# PG04_SHEET2.net
KiCad netlist of a schematic drawn in Altium Designer
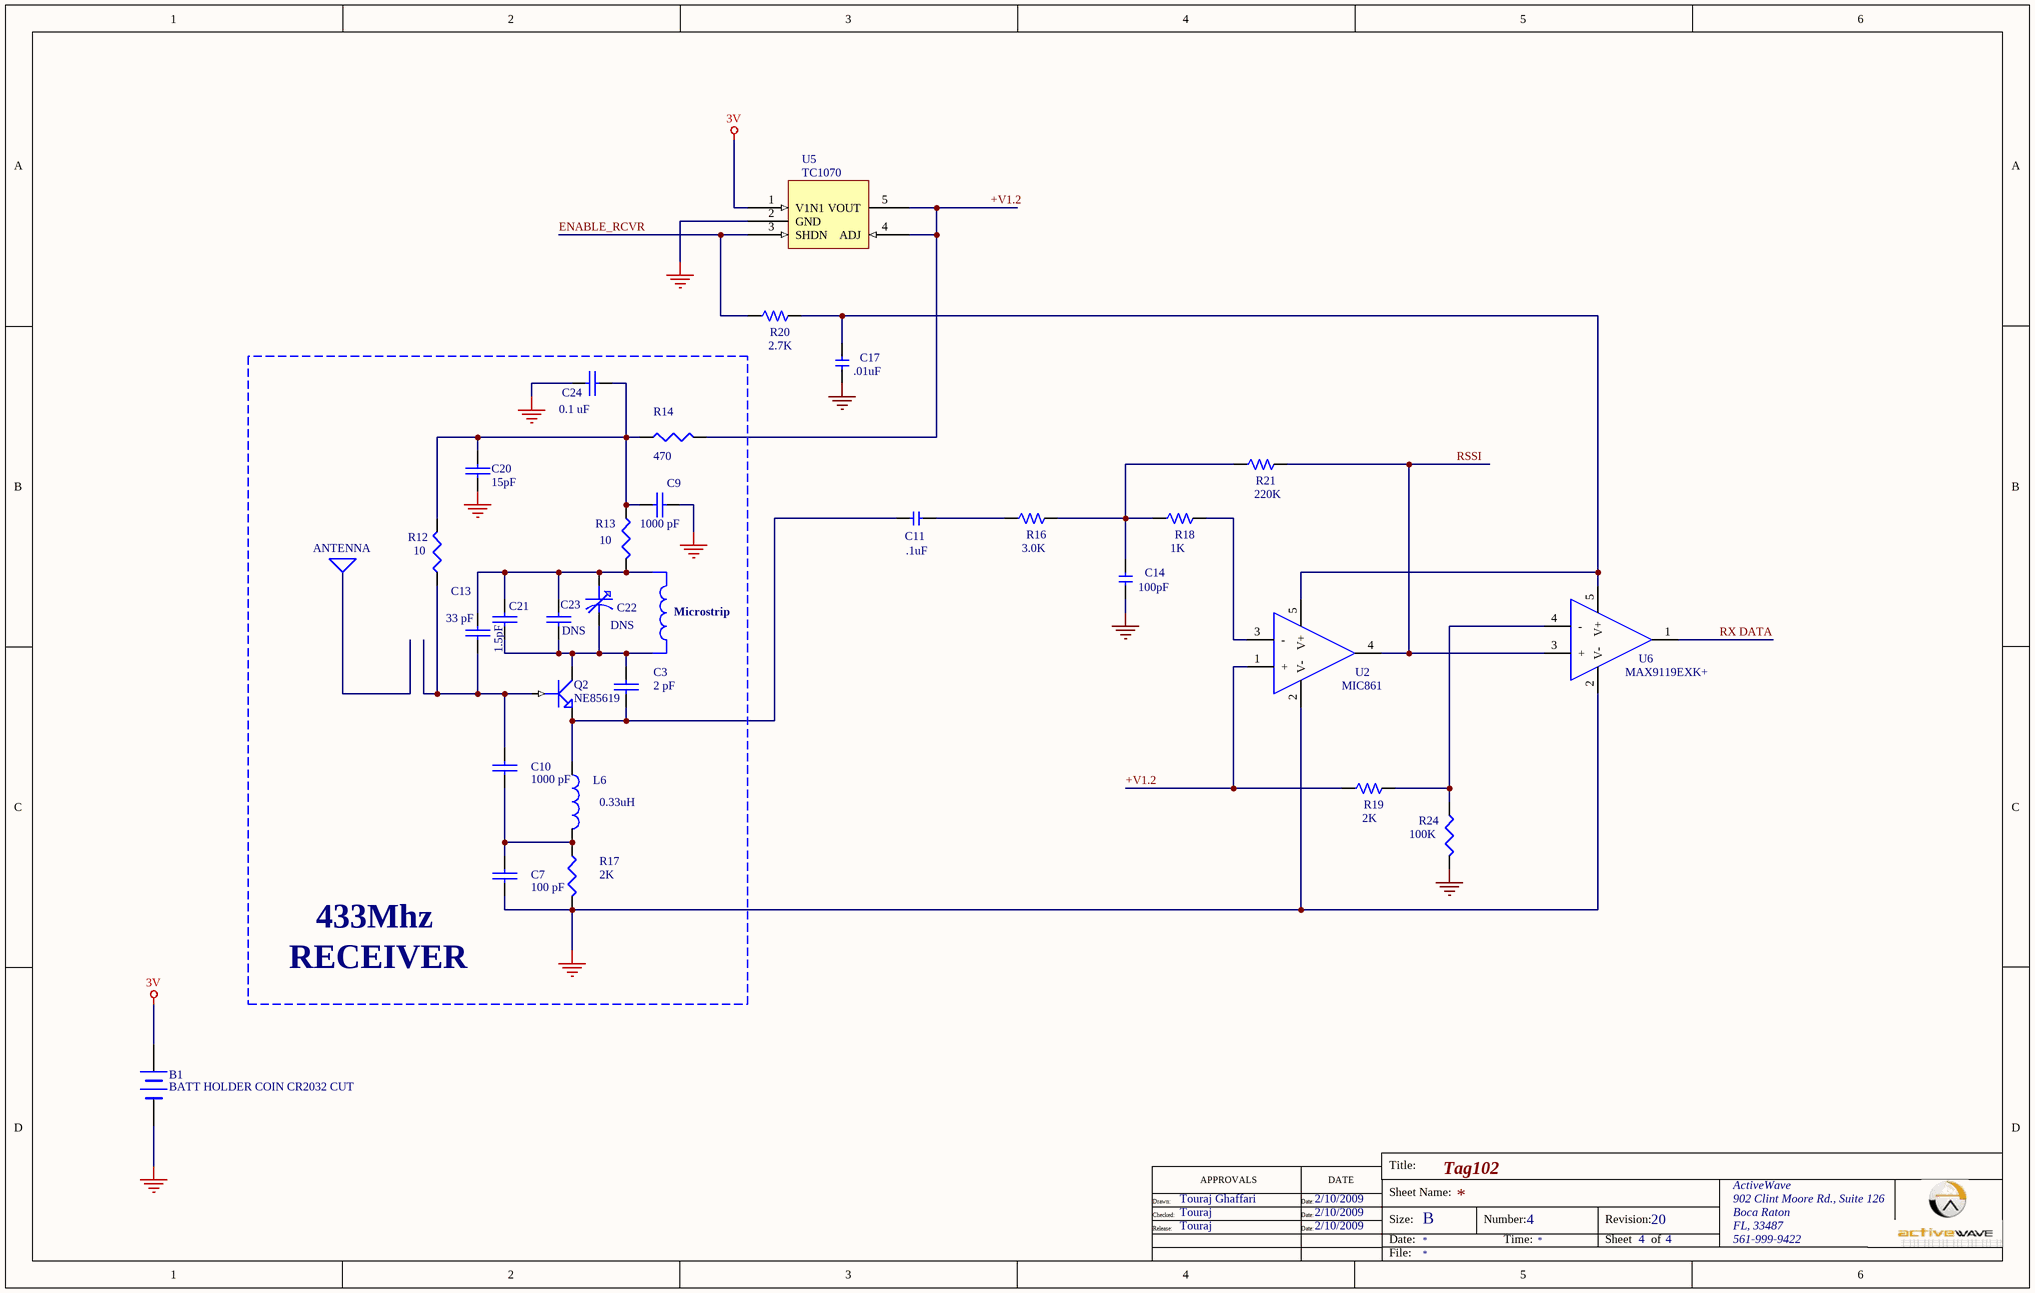
[diagram p0: PG04 SHEET2.schdoc]

(export (version "E")
  (design (tool "Eeschema 10.0.6"))
  (components
    (comp (ref "B1")
      (value "BATT HOLDER COIN CR2032 CUT")
      (footprint "BATT HOLDER COIN CR2032 CUT_020812")
      (description "Battery")
      (libsource (lib "*") (part "BATTERY"))
    )
    (comp (ref "C3")
      (value "2 pF")
      (footprint "0603")
      (description "Capacitor")
      (libsource (lib "*") (part "CAP"))
    )
    (comp (ref "C7")
      (value "100 pF")
      (footprint "0603")
      (description "Capacitor")
      (libsource (lib "*") (part "CAP"))
    )
    (comp (ref "C9")
      (value "1000 pF")
      (footprint "0603")
      (description "Capacitor")
      (libsource (lib "*") (part "CAP"))
    )
    (comp (ref "C10")
      (value "1000 pF")
      (footprint "0603")
      (description "Capacitor")
      (libsource (lib "*") (part "CAP"))
    )
    (comp (ref "C11") (value ".1uF") (footprint "0603") (libsource (lib "*") (part "C")))
    (comp (ref "C13")
      (value "33 pF")
      (footprint "0603")
      (description "Capacitor")
      (libsource (lib "*") (part "CAP"))
    )
    (comp (ref "C14") (value "100pF") (footprint "0603") (libsource (lib "*") (part "C")))
    (comp (ref "C17") (value ".01uF") (footprint "0603") (libsource (lib "*") (part "C")))
    (comp (ref "C20")
      (value "15pF")
      (footprint "0603")
      (description "Capacitor")
      (libsource (lib "*") (part "CAP"))
    )
    (comp (ref "C21")
      (value "1.5pF")
      (footprint "0603")
      (description "Capacitor")
      (libsource (lib "*") (part "CAP"))
    )
    (comp (ref "C22") (value "DNS") (footprint "0603") (libsource (lib "*") (part "CAPACITOR VAR")))
    (comp (ref "C23")
      (value "DNS")
      (footprint "0603")
      (description "Capacitor")
      (libsource (lib "*") (part "CAP"))
    )
    (comp (ref "C24")
      (value "0.1 uF")
      (footprint "0603")
      (description "Capacitor")
      (libsource (lib "*") (part "CAP"))
    )
    (comp (ref "L6") (value "0.33uH") (footprint "0603") (libsource (lib "*") (part "INDUCTOR")))
    (comp (ref "Q2")
      (value "NE85619")
      (footprint "3 PIN ULTRA SUPER MINI MOLD")
      (description "NPN Transistor")
      (libsource (lib "*") (part "NPN1"))
    )
    (comp (ref "R12") (value "10") (footprint "0603") (libsource (lib "*") (part "R")))
    (comp (ref "R13") (value "10") (footprint "0603") (libsource (lib "*") (part "R")))
    (comp (ref "R14") (value "470") (footprint "0603") (libsource (lib "*") (part "R")))
    (comp (ref "R16") (value "3.0K") (footprint "0603") (libsource (lib "") (part "R_1")))
    (comp (ref "R17") (value "2K") (footprint "0603") (libsource (lib "*") (part "RESISTOR")))
    (comp (ref "R18") (value "1K") (footprint "0603") (libsource (lib "") (part "R_1")))
    (comp (ref "R19") (value "2K") (footprint "0603") (libsource (lib "") (part "R_1")))
    (comp (ref "R20") (value "2.7K") (footprint "0603") (libsource (lib "") (part "R_1")))
    (comp (ref "R21") (value "220K") (footprint "0603") (libsource (lib "") (part "R_1")))
    (comp (ref "R24") (value "100K") (footprint "0603") (libsource (lib "*") (part "R")))
    (comp (ref "U2") (value "MIC861") (footprint "SC70") (libsource (lib "*") (part "OPAMP MIC861")))
    (comp (ref "U5") (value "TC1070") (footprint "SOT23-5A") (libsource (lib "*") (part "TC1070-2")))
    (comp (ref "U6")
      (value "MAX9119EXK+")
      (footprint "SC70")
      (libsource (lib "*") (part "COMPARATOR MAX9117"))
    )
  )
  (nets
    (net (code "1") (name "/+V1.2") (class "Default")
      (node (ref "R14") (pin "2") (pinfunction "2_2") (pintype "passive"))
      (node (ref "R19") (pin "1") (pinfunction "1_1") (pintype "passive"))
      (node (ref "U2") (pin "1") (pinfunction "+_1") (pintype "passive"))
      (node (ref "U5") (pin "4") (pinfunction "ADJ_4") (pintype "input"))
      (node (ref "U5") (pin "5") (pinfunction "VOUT_5") (pintype "power_in"))
    )
    (net (code "2") (name "/ENABLE_RCVR") (class "Default")
      (node (ref "R20") (pin "1") (pinfunction "1_1") (pintype "passive"))
      (node (ref "U5") (pin "3") (pinfunction "SHDN_3") (pintype "input"))
    )
    (net (code "3") (name "/RSSI") (class "Default")
      (node (ref "R21") (pin "2") (pinfunction "2_2") (pintype "passive"))
      (node (ref "U2") (pin "4") (pinfunction "OUT_4") (pintype "passive"))
      (node (ref "U6") (pin "3") (pinfunction "+_3") (pintype "passive"))
    )
    (net (code "4") (name "/RX DATA") (class "Default")
      (node (ref "U6") (pin "1") (pinfunction "OUT_1") (pintype "passive"))
    )
    (net (code "5") (name "3V") (class "Default")
      (node (ref "B1") (pin "2") (pinfunction "+_2") (pintype "passive"))
      (node (ref "U5") (pin "1") (pinfunction "V1N1_1") (pintype "input"))
    )
    (net (code "6") (name "GND") (class "Default")
      (node (ref "B1") (pin "1") (pinfunction "-_1") (pintype "passive"))
      (node (ref "C14") (pin "1") (pinfunction "1_1") (pintype "passive"))
      (node (ref "C17") (pin "1") (pinfunction "1_1") (pintype "passive"))
      (node (ref "C20") (pin "1") (pinfunction "1_1") (pintype "passive"))
      (node (ref "C24") (pin "1") (pinfunction "1_1") (pintype "passive"))
      (node (ref "C7") (pin "2") (pinfunction "2_2") (pintype "passive"))
      (node (ref "C9") (pin "2") (pinfunction "2_2") (pintype "passive"))
      (node (ref "R17") (pin "2") (pinfunction "2_2") (pintype "passive"))
      (node (ref "R24") (pin "2") (pinfunction "2_2") (pintype "passive"))
      (node (ref "U2") (pin "2") (pinfunction "V-_2") (pintype "passive"))
      (node (ref "U5") (pin "2") (pinfunction "GND_2") (pintype "power_in"))
      (node (ref "U6") (pin "2") (pinfunction "V-_2") (pintype "passive"))
    )
    (net (code "7") (name "Net-(C10-Pad1)") (class "Default")
      (node (ref "C10") (pin "1") (pinfunction "1_1") (pintype "passive"))
      (node (ref "C13") (pin "1") (pinfunction "1_1") (pintype "passive"))
      (node (ref "Q2") (pin "B") (pinfunction "B_B") (pintype "input"))
      (node (ref "R12") (pin "1") (pinfunction "1_1") (pintype "passive"))
    )
    (net (code "8") (name "Net-(C10-Pad2)") (class "Default")
      (node (ref "C10") (pin "2") (pinfunction "2_2") (pintype "passive"))
      (node (ref "C7") (pin "1") (pinfunction "1_1") (pintype "passive"))
      (node (ref "L6") (pin "2") (pinfunction "2_2") (pintype "passive"))
      (node (ref "R17") (pin "1") (pinfunction "1_1") (pintype "passive"))
    )
    (net (code "9") (name "Net-(C11-Pad1)") (class "Default")
      (node (ref "C11") (pin "1") (pinfunction "1_1") (pintype "passive"))
      (node (ref "C3") (pin "2") (pinfunction "2_2") (pintype "passive"))
      (node (ref "L6") (pin "1") (pinfunction "1_1") (pintype "passive"))
      (node (ref "Q2") (pin "E") (pinfunction "E_E") (pintype "passive"))
    )
    (net (code "10") (name "Net-(C11-Pad2)") (class "Default")
      (node (ref "C11") (pin "2") (pinfunction "2_2") (pintype "passive"))
      (node (ref "R16") (pin "1") (pinfunction "1_1") (pintype "passive"))
    )
    (net (code "11") (name "Net-(C13-Pad2)") (class "Default")
      (node (ref "C13") (pin "2") (pinfunction "2_2") (pintype "passive"))
      (node (ref "C21") (pin "1") (pinfunction "1_1") (pintype "passive"))
      (node (ref "C22") (pin "1") (pinfunction "1_1") (pintype "passive"))
      (node (ref "C23") (pin "1") (pinfunction "1_1") (pintype "passive"))
      (node (ref "R13") (pin "2") (pinfunction "2_2") (pintype "passive"))
    )
    (net (code "12") (name "Net-(C14-Pad2)") (class "Default")
      (node (ref "C14") (pin "2") (pinfunction "2_2") (pintype "passive"))
      (node (ref "R16") (pin "2") (pinfunction "2_2") (pintype "passive"))
      (node (ref "R18") (pin "1") (pinfunction "1_1") (pintype "passive"))
      (node (ref "R21") (pin "1") (pinfunction "1_1") (pintype "passive"))
    )
    (net (code "13") (name "Net-(C20-Pad2)") (class "Default")
      (node (ref "C20") (pin "2") (pinfunction "2_2") (pintype "passive"))
      (node (ref "C24") (pin "2") (pinfunction "2_2") (pintype "passive"))
      (node (ref "C9") (pin "1") (pinfunction "1_1") (pintype "passive"))
      (node (ref "R12") (pin "2") (pinfunction "2_2") (pintype "passive"))
      (node (ref "R13") (pin "1") (pinfunction "1_1") (pintype "passive"))
      (node (ref "R14") (pin "1") (pinfunction "1_1") (pintype "passive"))
    )
    (net (code "14") (name "Net-(C21-Pad2)") (class "Default")
      (node (ref "C21") (pin "2") (pinfunction "2_2") (pintype "passive"))
      (node (ref "C22") (pin "2") (pinfunction "2_2") (pintype "passive"))
      (node (ref "C23") (pin "2") (pinfunction "2_2") (pintype "passive"))
      (node (ref "C3") (pin "1") (pinfunction "1_1") (pintype "passive"))
      (node (ref "Q2") (pin "C") (pinfunction "C_C") (pintype "passive"))
    )
    (net (code "15") (name "Net-(U2--)") (class "Default")
      (node (ref "R18") (pin "2") (pinfunction "2_2") (pintype "passive"))
      (node (ref "U2") (pin "3") (pinfunction "-_3") (pintype "passive"))
    )
    (net (code "16") (name "Net-(U2-V+)") (class "Default")
      (node (ref "C17") (pin "2") (pinfunction "2_2") (pintype "passive"))
      (node (ref "R20") (pin "2") (pinfunction "2_2") (pintype "passive"))
      (node (ref "U2") (pin "5") (pinfunction "V+_5") (pintype "passive"))
      (node (ref "U6") (pin "5") (pinfunction "V+_5") (pintype "passive"))
    )
    (net (code "17") (name "Net-(U6--)") (class "Default")
      (node (ref "R19") (pin "2") (pinfunction "2_2") (pintype "passive"))
      (node (ref "R24") (pin "1") (pinfunction "1_1") (pintype "passive"))
      (node (ref "U6") (pin "4") (pinfunction "-_4") (pintype "passive"))
    )
  )
)
